# 31_1_Conector_USB.net
KiCad netlist of a schematic drawn in Altium Designer
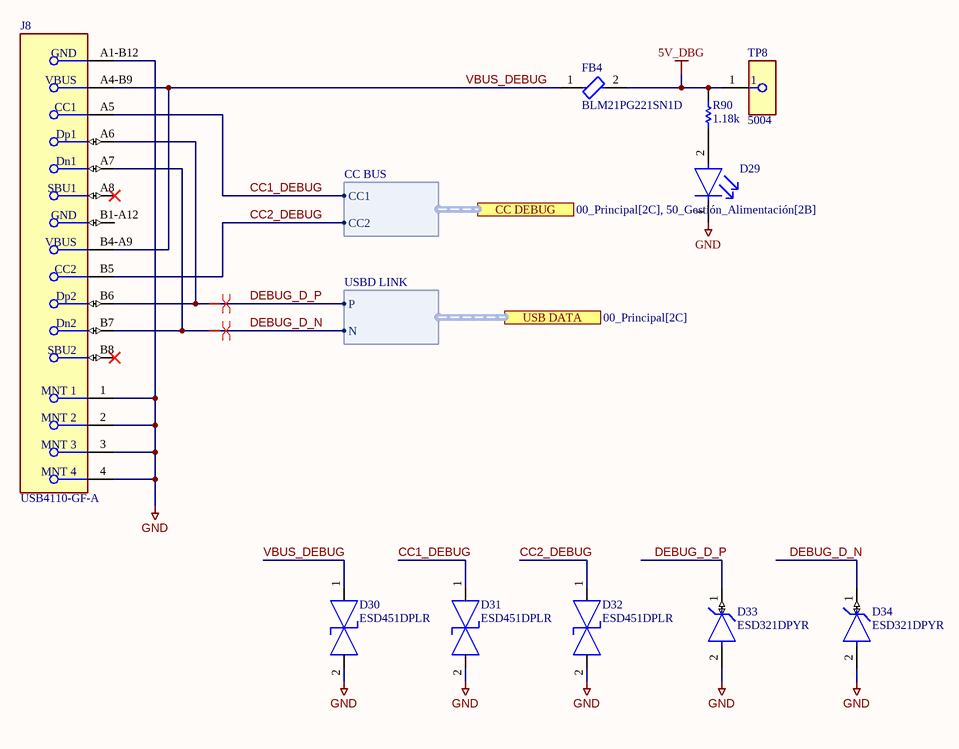
[diagram p0: 31_1_Conector_USB.SchDoc]

(export (version "E")
  (design (tool "Eeschema 10.0.6"))
  (components
    (comp (ref "D29")
      (value "APHD1608LZGCK")
      (footprint "FP-APHD1608LZGCK-MFG")
      (description "LED GREEN CLEAR 1608 SMD")
      (libsource (lib "Altium Content Vault") (part "8706943c75ba83719d021d2fdc84c58"))
    )
    (comp (ref "D30")
      (value "ESD451DPLR")
      (footprint "FP-DPL0002A_MFG")
      (description "0.5-pF, 5.5-V, 30-KV bidirectional ESD protection device in 0201 package 2-X2SON -40 to 125")
      (libsource (lib "Altium Content Vault") (part "ef80418522d6051962dd4b26d32e366"))
    )
    (comp (ref "D31")
      (value "ESD451DPLR")
      (footprint "FP-DPL0002A_MFG")
      (description "0.5-pF, 5.5-V, 30-KV bidirectional ESD protection device in 0201 package 2-X2SON -40 to 125")
      (libsource (lib "Altium Content Vault") (part "ef80418522d6051962dd4b26d32e366"))
    )
    (comp (ref "D32")
      (value "ESD451DPLR")
      (footprint "FP-DPL0002A_MFG")
      (description "0.5-pF, 5.5-V, 30-KV bidirectional ESD protection device in 0201 package 2-X2SON -40 to 125")
      (libsource (lib "Altium Content Vault") (part "ef80418522d6051962dd4b26d32e366"))
    )
    (comp (ref "D33")
      (value "ESD321DPYR")
      (footprint "FP-DPY0002A-MFG")
      (description "HDMI2.0 ESD PROTECTION")
      (fields
        (field (name "OCTOPART") "https://octopart.com/esd321dpyr-texas+instruments-94354200")
        (field (name "MANUFACTURER") "Texas Instruments")
      )
      (libsource (lib "Altium Content Vault") (part "66ee42db3b8e3650e8893baa18e0b41"))
    )
    (comp (ref "D34")
      (value "ESD321DPYR")
      (footprint "FP-DPY0002A-MFG")
      (description "HDMI2.0 ESD PROTECTION")
      (fields
        (field (name "OCTOPART") "https://octopart.com/esd321dpyr-texas+instruments-94354200")
        (field (name "MANUFACTURER") "Texas Instruments")
      )
      (libsource (lib "Altium Content Vault") (part "66ee42db3b8e3650e8893baa18e0b41"))
    )
    (comp (ref "FB4")
      (value "BLM21PG221SN1D")
      (footprint "FP-BLM21-0_2-t0_85-e0_5-IPC_B")
      (description "Chip Ferrite Bead, 0805, 220Ω @ 100MHz, 0.045Ω, 25%, 2A")
      (fields (field (name "TOLERANCE") "25%"))
      (libsource (lib "Altium Content Vault") (part "5f30dd21d616792df468990f7003faa"))
    )
    (comp (ref "J8")
      (value "USB4110-GF-A")
      (footprint "FP-USB4110-GF-A-MFG")
      (description "CONN USB 2.0 TYPE-C R/A SMT")
      (fields
        (field (name "OCTOPART") "https://octopart.com/usb4110-gf-a-gct-103941985")
        (field (name "MANUFACTURER") "GCT")
      )
      (libsource (lib "Altium Content Vault") (part "e23f2b38bb3c3f98e683ebab9ede730"))
    )
    (comp (ref "R90")
      (value "1.18k")
      (footprint "RESC1005X40X25NL05T05")
      (fields (field (name "PART NUMBER") "ERJ-2RKF1181X") (field (name "MANUFACTURER") "Panasonic"))
      (libsource (lib "Altium Content Vault") (part "RES"))
    )
    (comp (ref "TP8")
      (value "5004")
      (footprint "FP-5004-MFG")
      (description "PC TEST POINT MINIATURE YELLOW")
      (fields
        (field (name "MANUFACTURER") "Keystone")
        (field (name "OCTOPART") "https://octopart.com/5004-keystone-28591")
      )
      (libsource (lib "Altium Content Vault") (part "98815daf2f2c152b0c43f5ab9800df6"))
    )
  )
  (nets
    (net (code "5") (name "/CC1_DEBUG") (class "Default")
      (node (ref "D31") (pin "1") (pinfunction "1_IO_1") (pintype "passive"))
      (node (ref "J8") (pin "A5") (pinfunction "CC1_A5") (pintype "passive"))
    )
    (net (code "6") (name "/CC2_DEBUG") (class "Default")
      (node (ref "D32") (pin "1") (pinfunction "1_IO_1") (pintype "passive"))
      (node (ref "J8") (pin "B5") (pinfunction "CC2_B5") (pintype "passive"))
    )
    (net (code "7") (name "/DEBUG_D_N") (class "Default")
      (node (ref "D34") (pin "1") (pinfunction "IO_1") (pintype "bidirectional"))
      (node (ref "J8") (pin "A7") (pinfunction "Dn1_A7") (pintype "bidirectional"))
      (node (ref "J8") (pin "B7") (pinfunction "Dn2_B7") (pintype "bidirectional"))
    )
    (net (code "8") (name "/DEBUG_D_P") (class "Default")
      (node (ref "D33") (pin "1") (pinfunction "IO_1") (pintype "bidirectional"))
      (node (ref "J8") (pin "A6") (pinfunction "Dp1_A6") (pintype "bidirectional"))
      (node (ref "J8") (pin "B6") (pinfunction "Dp2_B6") (pintype "bidirectional"))
    )
    (net (code "9") (name "/VBUS_DEBUG") (class "Default")
      (node (ref "D30") (pin "1") (pinfunction "1_IO_1") (pintype "passive"))
      (node (ref "FB4") (pin "1") (pinfunction "1_1") (pintype "passive"))
      (node (ref "J8") (pin "A4-B9") (pinfunction "VBUS_A4-B9") (pintype "power_in"))
      (node (ref "J8") (pin "B4-A9") (pinfunction "VBUS_B4-A9") (pintype "power_in"))
    )
    (net (code "12") (name "5V_DBG") (class "Default")
      (node (ref "FB4") (pin "2") (pinfunction "2_2") (pintype "passive"))
      (node (ref "R90") (pin "2") (pinfunction "2_2") (pintype "passive"))
      (node (ref "TP8") (pin "1") (pinfunction "1_1") (pintype "passive"))
    )
    (net (code "13") (name "GND") (class "Default")
      (node (ref "D29") (pin "1") (pinfunction "C_1") (pintype "passive"))
      (node (ref "D30") (pin "2") (pinfunction "2_IO_2") (pintype "passive"))
      (node (ref "D31") (pin "2") (pinfunction "2_IO_2") (pintype "passive"))
      (node (ref "D32") (pin "2") (pinfunction "2_IO_2") (pintype "passive"))
      (node (ref "D33") (pin "2") (pinfunction "GND_2") (pintype "power_in"))
      (node (ref "D34") (pin "2") (pinfunction "GND_2") (pintype "power_in"))
      (node (ref "J8") (pin "1") (pinfunction "MNT_1_1") (pintype "passive"))
      (node (ref "J8") (pin "2") (pinfunction "MNT_2_2") (pintype "passive"))
      (node (ref "J8") (pin "3") (pinfunction "MNT_3_3") (pintype "passive"))
      (node (ref "J8") (pin "4") (pinfunction "MNT_4_4") (pintype "passive"))
      (node (ref "J8") (pin "A1-B12") (pinfunction "GND_A1-B12") (pintype "passive"))
    )
    (net (code "14") (name "Net-(D29-A)") (class "Default")
      (node (ref "D29") (pin "2") (pinfunction "A_2") (pintype "passive"))
      (node (ref "R90") (pin "1") (pinfunction "1_1") (pintype "passive"))
    )
    (net (code "15") (name "unconnected-(J8-GND-PadB1-A12)") (class "Default")
      (node (ref "J8") (pin "B1-A12") (pinfunction "GND_B1-A12") (pintype "bidirectional"))
    )
    (net (code "16") (name "unconnected-(J8-SBU1-PadA8)") (class "Default")
      (node (ref "J8") (pin "A8") (pinfunction "SBU1_A8") (pintype "bidirectional+no_connect"))
    )
    (net (code "17") (name "unconnected-(J8-SBU2-PadB8)") (class "Default")
      (node (ref "J8") (pin "B8") (pinfunction "SBU2_B8") (pintype "bidirectional+no_connect"))
    )
  )
)
